# DA16200_Thing_Plus.net
KiCad netlist of a schematic drawn in EAGLE
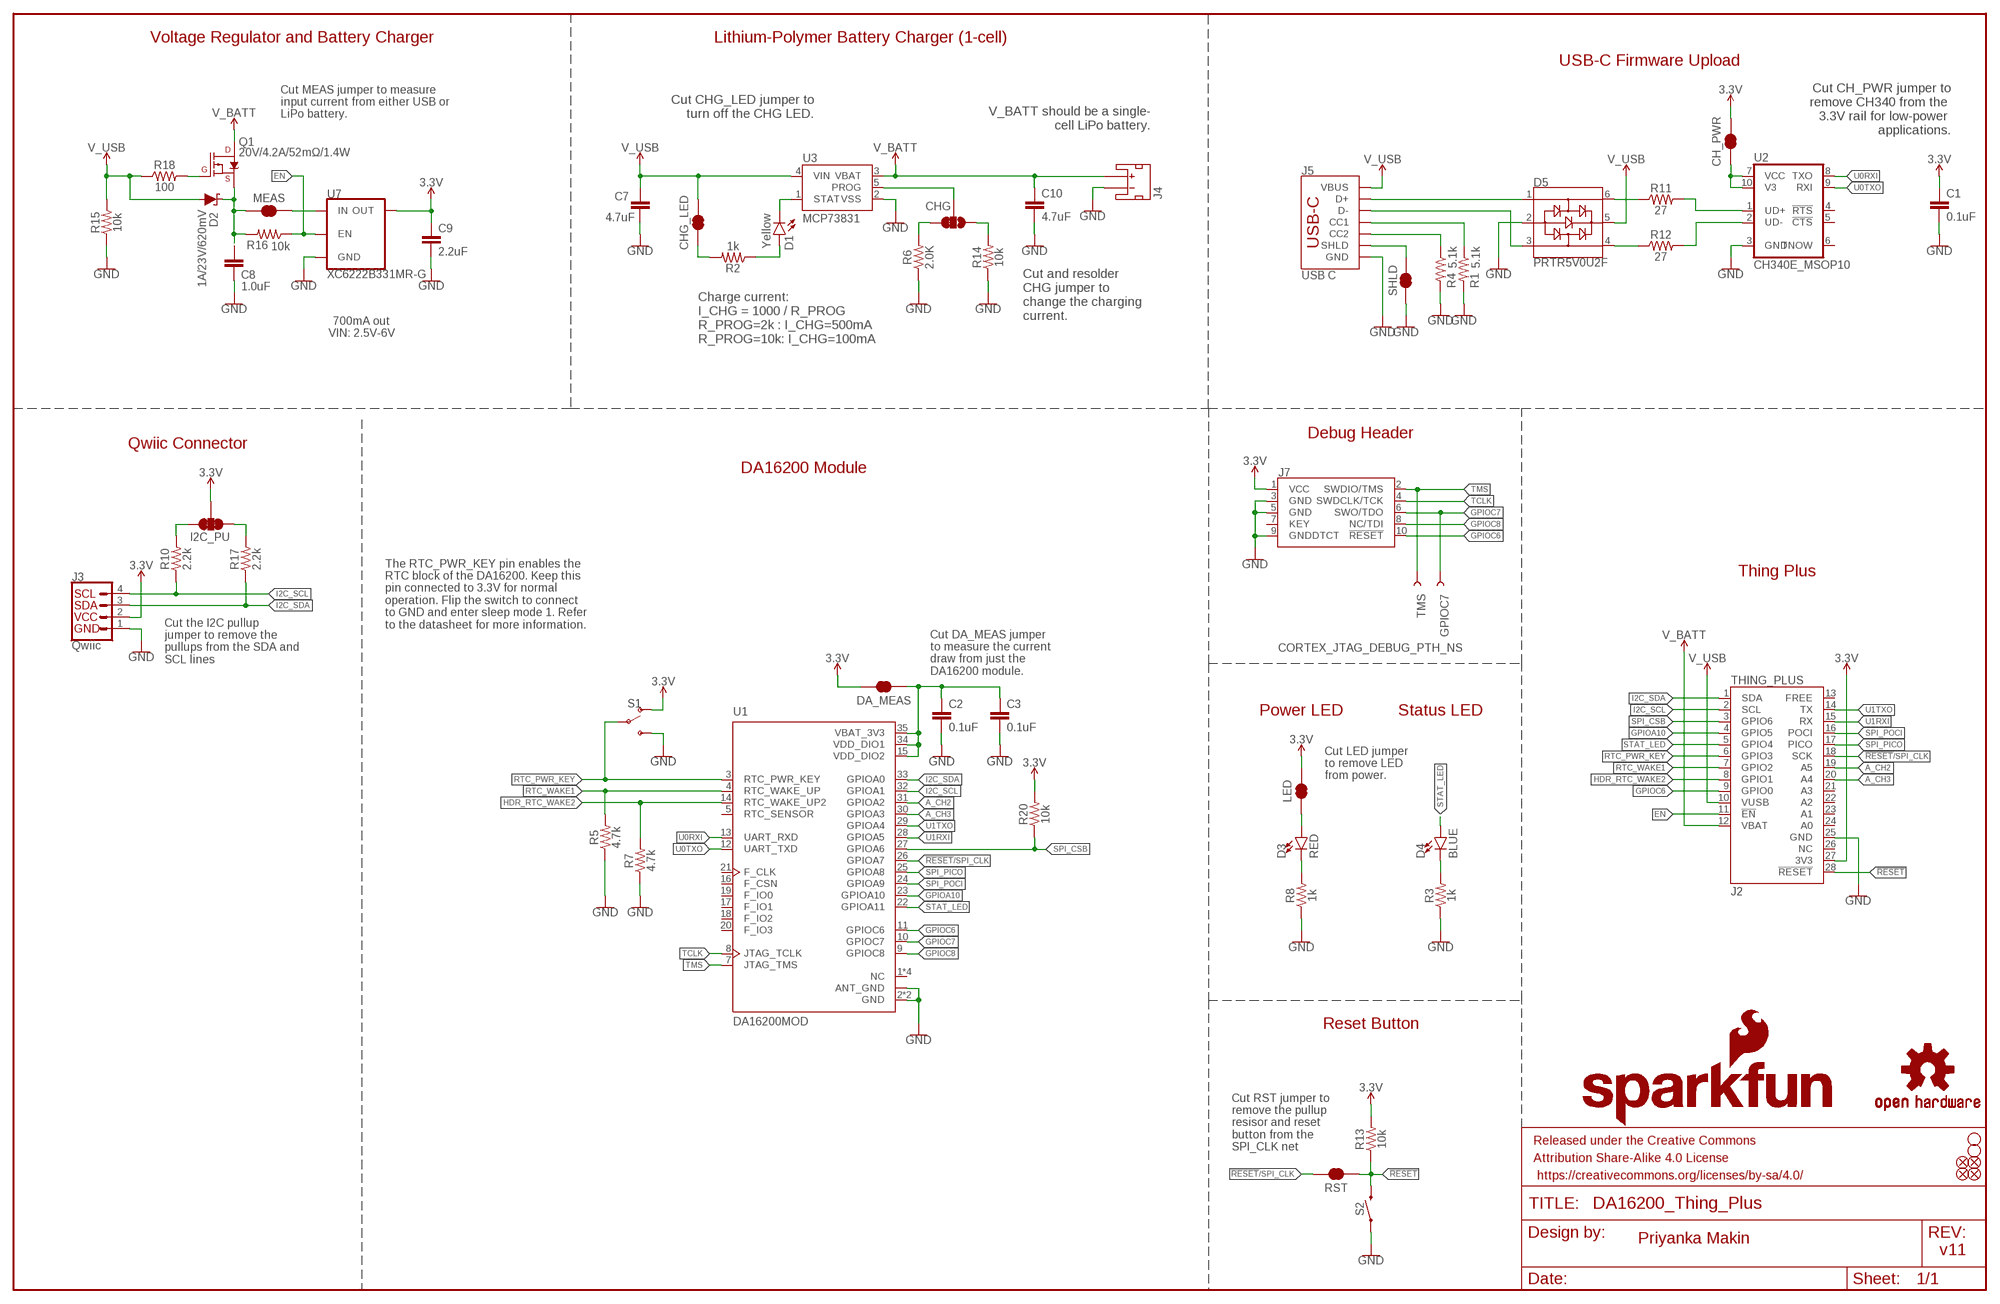
[diagram p0: schematic, sheet 1]

(export (version "E")
  (design (tool "Eeschema 10.0.6"))
  (components
    (comp (ref "C1")
      (value "0.1uF")
      (footprint "eagle-import:0402-TIGHT")
      (libsource (lib "eagle-import") (part "0.1UF-0402T-16V-10%"))
    )
    (comp (ref "C2")
      (value "0.1uF")
      (footprint "eagle-import:0402-TIGHT")
      (libsource (lib "eagle-import") (part "0.1UF-0402T-16V-10%"))
    )
    (comp (ref "C3")
      (value "0.1uF")
      (footprint "eagle-import:0402-TIGHT")
      (libsource (lib "eagle-import") (part "0.1UF-0402T-16V-10%"))
    )
    (comp (ref "C7")
      (value "4.7uF")
      (footprint "eagle-import:0402-TIGHT")
      (libsource (lib "eagle-import") (part "4.7UF-0402_TIGHT-6.3V-20%-X5R"))
    )
    (comp (ref "C8")
      (value "1.0uF")
      (footprint "eagle-import:0402-TIGHT")
      (libsource (lib "eagle-import") (part "1.0UF-0402T-16V-10%"))
    )
    (comp (ref "C9")
      (value "2.2uF")
      (footprint "eagle-import:0402-TIGHT")
      (libsource (lib "eagle-import") (part "2.2UF-0402_TIGHT-10V-10%-X5R"))
    )
    (comp (ref "C10")
      (value "4.7uF")
      (footprint "eagle-import:0402-TIGHT")
      (libsource (lib "eagle-import") (part "4.7UF-0402_TIGHT-6.3V-20%-X5R"))
    )
    (comp (ref "CHG")
      (value "JUMPER-SMT_3_1-NC_TRACE_SILK")
      (footprint "eagle-import:SMT-JUMPER_3_1-NC_TRACE_SILK")
      (libsource (lib "eagle-import") (part "JUMPER-SMT_3_1-NC_TRACE_SILK"))
    )
    (comp (ref "CHG_LED")
      (value "JUMPER-SMT_2_NC_TRACE_SILK")
      (footprint "eagle-import:SMT-JUMPER_2_NC_TRACE_SILK")
      (libsource (lib "eagle-import") (part "JUMPER-SMT_2_NC_TRACE_SILK"))
    )
    (comp (ref "CH_PWR")
      (value "JUMPER-SMT_2_NC_TRACE_SILK")
      (footprint "eagle-import:SMT-JUMPER_2_NC_TRACE_SILK")
      (libsource (lib "eagle-import") (part "JUMPER-SMT_2_NC_TRACE_SILK"))
    )
    (comp (ref "D1")
      (value "Yellow")
      (footprint "eagle-import:LED-0603")
      (libsource (lib "eagle-import") (part "LED-YELLOW0603"))
    )
    (comp (ref "D2")
      (value "1A/23V/620mV")
      (footprint "eagle-import:SOD-323")
      (libsource (lib "eagle-import") (part "DIODE-SCHOTTKY-BAT20J"))
    )
    (comp (ref "D3")
      (value "RED")
      (footprint "eagle-import:LED-0603")
      (libsource (lib "eagle-import") (part "LED-RED0603"))
    )
    (comp (ref "D4")
      (value "BLUE")
      (footprint "eagle-import:LED-0603")
      (libsource (lib "eagle-import") (part "LED-BLUE0603"))
    )
    (comp (ref "D5")
      (value "PRTR5V0U2F")
      (footprint "eagle-import:SOT886")
      (libsource (lib "eagle-import") (part "PRTR5V0U2F"))
    )
    (comp (ref "DA_MEAS")
      (value "JUMPER-SMT_2_NC_TRACE_SILK")
      (footprint "eagle-import:SMT-JUMPER_2_NC_TRACE_SILK")
      (libsource (lib "eagle-import") (part "JUMPER-SMT_2_NC_TRACE_SILK"))
    )
    (comp (ref "FD1")
      (value "FIDUCIALUFIDUCIAL")
      (footprint "eagle-import:FIDUCIAL-MICRO")
      (libsource (lib "eagle-import") (part "FIDUCIALUFIDUCIAL"))
    )
    (comp (ref "FD2")
      (value "FIDUCIALUFIDUCIAL")
      (footprint "eagle-import:FIDUCIAL-MICRO")
      (libsource (lib "eagle-import") (part "FIDUCIALUFIDUCIAL"))
    )
    (comp (ref "FD3")
      (value "FIDUCIALUFIDUCIAL")
      (footprint "eagle-import:FIDUCIAL-MICRO")
      (libsource (lib "eagle-import") (part "FIDUCIALUFIDUCIAL"))
    )
    (comp (ref "FD4")
      (value "FIDUCIALUFIDUCIAL")
      (footprint "eagle-import:FIDUCIAL-MICRO")
      (libsource (lib "eagle-import") (part "FIDUCIALUFIDUCIAL"))
    )
    (comp (ref "FRAME1")
      (value "FRAME-LEDGER")
      (footprint "eagle-import:CREATIVE_COMMONS")
      (libsource (lib "eagle-import") (part "FRAME-LEDGER"))
    )
    (comp (ref "GPIOC7")
      (value "TEST-POINT3")
      (footprint "eagle-import:PAD.03X.03")
      (libsource (lib "eagle-import") (part "TEST-POINT3"))
    )
    (comp (ref "H3")
      (value "STAND-OFF")
      (footprint "eagle-import:STAND-OFF")
      (libsource (lib "eagle-import") (part "STAND-OFF"))
    )
    (comp (ref "H4")
      (value "STAND-OFF")
      (footprint "eagle-import:STAND-OFF")
      (libsource (lib "eagle-import") (part "STAND-OFF"))
    )
    (comp (ref "I2C_PU")
      (value "JUMPER-SMT_3_2-NC_TRACE_SILK")
      (footprint "eagle-import:SMT-JUMPER_3_2-NC_TRACE_SILK")
      (libsource (lib "eagle-import") (part "JUMPER-SMT_3_2-NC_TRACE_SILK"))
    )
    (comp (ref "J2")
      (value "THING_PLUS")
      (footprint "eagle-import:THING_PLUS")
      (libsource (lib "eagle-import") (part "THING_PLUS"))
    )
    (comp (ref "J3")
      (value "Qwiic")
      (footprint "eagle-import:JST04_1MM_RA")
      (libsource (lib "eagle-import") (part "QWIIC_CONNECTORJS-1MM"))
    )
    (comp (ref "J4")
      (value "JST_2MM_MALE")
      (footprint "eagle-import:JST-2-SMD")
      (libsource (lib "eagle-import") (part "JST_2MM_MALE"))
    )
    (comp (ref "J5")
      (value "USB C")
      (footprint "eagle-import:USB-C-16P-4LAYER-ISOLATED")
      (libsource (lib "eagle-import") (part "USB_C_4-LAYER-ISOLATED"))
    )
    (comp (ref "J7")
      (value "CORTEX_JTAG_DEBUG_PTH_NS")
      (footprint "eagle-import:2X5-PTH-1.27MM-NO_SILK")
      (libsource (lib "eagle-import") (part "CORTEX_JTAG_DEBUG_PTH_NS"))
    )
    (comp (ref "LED")
      (value "JUMPER-SMT_2_NC_TRACE_SILK")
      (footprint "eagle-import:SMT-JUMPER_2_NC_TRACE_SILK")
      (libsource (lib "eagle-import") (part "JUMPER-SMT_2_NC_TRACE_SILK"))
    )
    (comp (ref "LOGO1")
      (value "OSHW-LOGOS")
      (footprint "eagle-import:OSHW-LOGO-S")
      (libsource (lib "eagle-import") (part "OSHW-LOGOS"))
    )
    (comp (ref "LOGO2")
      (value "SFE_LOGO_NAME_FLAME.1_INCH")
      (footprint "eagle-import:SFE_LOGO_NAME_FLAME_.1")
      (libsource (lib "eagle-import") (part "SFE_LOGO_NAME_FLAME.1_INCH"))
    )
    (comp (ref "MEAS")
      (value "JUMPER-COMBO_2_NC_TRACE")
      (footprint "eagle-import:COMBO-JUMPER_2_NC_TRACE")
      (libsource (lib "eagle-import") (part "JUMPER-COMBO_2_NC_TRACE"))
    )
    (comp (ref "Q1")
      (value "20V/4.2A/52mΩ/1.4W")
      (footprint "eagle-import:SOT23-3")
      (libsource (lib "eagle-import") (part "MOSFET_PCH-DMG2305UX-7"))
    )
    (comp (ref "R1")
      (value "5.1k")
      (footprint "eagle-import:0402-TIGHT")
      (libsource (lib "eagle-import") (part "5.1KOHM-0402T-1/16W-1%"))
    )
    (comp (ref "R2")
      (value "1k")
      (footprint "eagle-import:0402-TIGHT")
      (libsource (lib "eagle-import") (part "1KOHM-0402T-1/16W-1%"))
    )
    (comp (ref "R3")
      (value "1k")
      (footprint "eagle-import:0402-TIGHT")
      (libsource (lib "eagle-import") (part "1KOHM-0402T-1/16W-1%"))
    )
    (comp (ref "R4")
      (value "5.1k")
      (footprint "eagle-import:0402-TIGHT")
      (libsource (lib "eagle-import") (part "5.1KOHM-0402T-1/16W-1%"))
    )
    (comp (ref "R5")
      (value "4.7k")
      (footprint "eagle-import:0402-TIGHT")
      (libsource (lib "eagle-import") (part "4.7KOHM-0402T-1/16W-1%"))
    )
    (comp (ref "R6")
      (value "2.0K")
      (footprint "eagle-import:0402-TIGHT")
      (libsource (lib "eagle-import") (part "2.0KOHM-0402T-1/16W-1%"))
    )
    (comp (ref "R7")
      (value "4.7k")
      (footprint "eagle-import:0402-TIGHT")
      (libsource (lib "eagle-import") (part "4.7KOHM-0402T-1/16W-1%"))
    )
    (comp (ref "R8")
      (value "1k")
      (footprint "eagle-import:0402-TIGHT")
      (libsource (lib "eagle-import") (part "1KOHM-0402T-1/16W-1%"))
    )
    (comp (ref "R10")
      (value "2.2k")
      (footprint "eagle-import:0402-TIGHT")
      (libsource (lib "eagle-import") (part "2.2KOHM-0402T-1/16W-1%"))
    )
    (comp (ref "R11")
      (value "27")
      (footprint "eagle-import:0402-TIGHT")
      (libsource (lib "eagle-import") (part "27OHM"))
    )
    (comp (ref "R12")
      (value "27")
      (footprint "eagle-import:0402-TIGHT")
      (libsource (lib "eagle-import") (part "27OHM"))
    )
    (comp (ref "R13")
      (value "10k")
      (footprint "eagle-import:0402-TIGHT")
      (libsource (lib "eagle-import") (part "10KOHM-0402T-1/16W-1%"))
    )
    (comp (ref "R14")
      (value "10k")
      (footprint "eagle-import:0402-TIGHT")
      (libsource (lib "eagle-import") (part "10KOHM-0402T-1/16W-1%"))
    )
    (comp (ref "R15")
      (value "10k")
      (footprint "eagle-import:0402-TIGHT")
      (libsource (lib "eagle-import") (part "10KOHM-0402T-1/16W-1%"))
    )
    (comp (ref "R16")
      (value "10k")
      (footprint "eagle-import:0402-TIGHT")
      (libsource (lib "eagle-import") (part "10KOHM-0402T-1/16W-1%"))
    )
    (comp (ref "R17")
      (value "2.2k")
      (footprint "eagle-import:0402-TIGHT")
      (libsource (lib "eagle-import") (part "2.2KOHM-0402T-1/16W-1%"))
    )
    (comp (ref "R18")
      (value "100")
      (footprint "eagle-import:0402-TIGHT")
      (libsource (lib "eagle-import") (part "100OHM-0402-TIGHT-1/16W-1%"))
    )
    (comp (ref "R20")
      (value "10k")
      (footprint "eagle-import:0402-TIGHT")
      (libsource (lib "eagle-import") (part "10KOHM-0402T-1/16W-1%"))
    )
    (comp (ref "RST")
      (value "JUMPER-SMT_2_NC_TRACE_SILK")
      (footprint "eagle-import:SMT-JUMPER_2_NC_TRACE_SILK")
      (libsource (lib "eagle-import") (part "JUMPER-SMT_2_NC_TRACE_SILK"))
    )
    (comp (ref "S1")
      (value "SWITCH-SPDT-SMD-AYZ0202")
      (footprint "eagle-import:SWITCH_DPDT_SMD_AYZ0202")
      (libsource (lib "eagle-import") (part "SWITCH-SPDT-SMD-AYZ0202"))
    )
    (comp (ref "S2")
      (value "MOMENTARY-SWITCH-SPST-SMD-5.2MM-TALL")
      (footprint "eagle-import:TACTILE_SWITCH_SMD_5.2MM")
      (libsource (lib "eagle-import") (part "MOMENTARY-SWITCH-SPST-SMD-5.2MM-TALL"))
    )
    (comp (ref "SHLD")
      (value "JUMPER-SMT_2_NC_TRACE_SILK")
      (footprint "eagle-import:SMT-JUMPER_2_NC_TRACE_SILK")
      (libsource (lib "eagle-import") (part "JUMPER-SMT_2_NC_TRACE_SILK"))
    )
    (comp (ref "TMS")
      (value "TEST-POINT3")
      (footprint "eagle-import:PAD.03X.03")
      (libsource (lib "eagle-import") (part "TEST-POINT3"))
    )
    (comp (ref "U1")
      (value "DA16200MOD")
      (footprint "eagle-import:XCVR_DA16200MOD-AAC4WA32")
      (libsource (lib "eagle-import") (part "DA16200MOD-AAC4WA32"))
    )
    (comp (ref "U2")
      (value "CH340E_MSOP10")
      (footprint "eagle-import:MSOP10")
      (libsource (lib "eagle-import") (part "CH340E_MSOP10"))
    )
    (comp (ref "U3")
      (value "MCP73831")
      (footprint "eagle-import:SOT23-5")
      (libsource (lib "eagle-import") (part "MCP73831"))
    )
    (comp (ref "U7")
      (value "XC6222B331MR-G")
      (footprint "eagle-import:SOT23-5")
      (libsource (lib "eagle-import") (part "XC6222B331MR-G"))
    )
  )
  (nets
    (net (code "1") (name "/~{RESET}") (class "Default")
      (node (ref "J2") (pin "28") (pinfunction "~{RESET}_28") (pintype "bidirectional"))
      (node (ref "R13") (pin "1") (pinfunction "1_1") (pintype "passive"))
      (node (ref "RST") (pin "1") (pinfunction "1_1") (pintype "passive"))
      (node (ref "S2") (pin "3") (pinfunction "2_3") (pintype "passive"))
    )
    (net (code "2") (name "/~{RESET}{slash}SPI_CLK") (class "Default")
      (node (ref "J2") (pin "18") (pinfunction "SCK_18") (pintype "bidirectional"))
      (node (ref "RST") (pin "2") (pinfunction "2_2") (pintype "passive"))
      (node (ref "U1") (pin "26") (pinfunction "GPIOA7_26") (pintype "bidirectional"))
    )
    (net (code "3") (name "3.3V") (class "Default")
      (node (ref "C1") (pin "1") (pinfunction "1_1") (pintype "passive"))
      (node (ref "C9") (pin "1") (pinfunction "1_1") (pintype "passive"))
      (node (ref "CH_PWR") (pin "2") (pinfunction "2_2") (pintype "passive"))
      (node (ref "DA_MEAS") (pin "2") (pinfunction "2_2") (pintype "passive"))
      (node (ref "I2C_PU") (pin "2") (pinfunction "2_2") (pintype "passive"))
      (node (ref "J2") (pin "27") (pinfunction "3V3_27") (pintype "bidirectional"))
      (node (ref "J3") (pin "2") (pinfunction "2_2") (pintype "power_in"))
      (node (ref "J7") (pin "1") (pinfunction "VCC_1") (pintype "bidirectional"))
      (node (ref "LED") (pin "2") (pinfunction "2_2") (pintype "passive"))
      (node (ref "R13") (pin "2") (pinfunction "2_2") (pintype "passive"))
      (node (ref "R20") (pin "2") (pinfunction "2_2") (pintype "passive"))
      (node (ref "S1") (pin "1") (pinfunction "O_1") (pintype "passive"))
      (node (ref "U7") (pin "5") (pinfunction "OUT_5") (pintype "passive"))
    )
    (net (code "4") (name "A_CH2") (class "Default")
      (node (ref "J2") (pin "19") (pinfunction "A5_19") (pintype "bidirectional"))
      (node (ref "U1") (pin "31") (pinfunction "GPIOA2_31") (pintype "bidirectional"))
    )
    (net (code "5") (name "A_CH3") (class "Default")
      (node (ref "J2") (pin "20") (pinfunction "A4_20") (pintype "bidirectional"))
      (node (ref "U1") (pin "30") (pinfunction "GPIOA3_30") (pintype "bidirectional"))
    )
    (net (code "6") (name "EN") (class "Default")
      (node (ref "J2") (pin "11") (pinfunction "~{EN}_11") (pintype "bidirectional"))
      (node (ref "R16") (pin "1") (pinfunction "1_1") (pintype "passive"))
      (node (ref "U7") (pin "3") (pinfunction "EN_3") (pintype "input"))
    )
    (net (code "7") (name "GND") (class "Default")
      (node (ref "C1") (pin "2") (pinfunction "2_2") (pintype "passive"))
      (node (ref "C10") (pin "2") (pinfunction "2_2") (pintype "passive"))
      (node (ref "C2") (pin "2") (pinfunction "2_2") (pintype "passive"))
      (node (ref "C3") (pin "2") (pinfunction "2_2") (pintype "passive"))
      (node (ref "C7") (pin "2") (pinfunction "2_2") (pintype "passive"))
      (node (ref "C8") (pin "2") (pinfunction "2_2") (pintype "passive"))
      (node (ref "C9") (pin "2") (pinfunction "2_2") (pintype "passive"))
      (node (ref "D5") (pin "2") (pinfunction "2_2") (pintype "power_in"))
      (node (ref "J2") (pin "25") (pinfunction "GND_25") (pintype "bidirectional"))
      (node (ref "J3") (pin "1") (pinfunction "1_1") (pintype "power_in"))
      (node (ref "J4") (pin "1") (pinfunction "-_1") (pintype "bidirectional"))
      (node (ref "J5") (pin "GND") (pinfunction "GND_GND") (pintype "bidirectional"))
      (node (ref "J5") (pin "GND2") (pinfunction "GND_GND2") (pintype "bidirectional"))
      (node (ref "J7") (pin "3") (pinfunction "GND_3") (pintype "bidirectional"))
      (node (ref "J7") (pin "5") (pinfunction "GND_5") (pintype "bidirectional"))
      (node (ref "J7") (pin "9") (pinfunction "GNDDTCT_9") (pintype "bidirectional"))
      (node (ref "R1") (pin "2") (pinfunction "2_2") (pintype "passive"))
      (node (ref "R14") (pin "1") (pinfunction "1_1") (pintype "passive"))
      (node (ref "R15") (pin "1") (pinfunction "1_1") (pintype "passive"))
      (node (ref "R3") (pin "1") (pinfunction "1_1") (pintype "passive"))
      (node (ref "R4") (pin "2") (pinfunction "2_2") (pintype "passive"))
      (node (ref "R5") (pin "1") (pinfunction "1_1") (pintype "passive"))
      (node (ref "R6") (pin "1") (pinfunction "1_1") (pintype "passive"))
      (node (ref "R7") (pin "1") (pinfunction "1_1") (pintype "passive"))
      (node (ref "R8") (pin "1") (pinfunction "1_1") (pintype "passive"))
      (node (ref "S1") (pin "3") (pinfunction "S_3") (pintype "passive"))
      (node (ref "S2") (pin "1") (pinfunction "1_1") (pintype "passive"))
      (node (ref "SHLD") (pin "1") (pinfunction "1_1") (pintype "passive"))
      (node (ref "U1") (pin "2") (pinfunction "GND_2") (pintype "power_in"))
      (node (ref "U1") (pin "ANT_GND") (pinfunction "ANT_GND_ANT_GND") (pintype "power_in"))
      (node (ref "U1") (pin "GND") (pinfunction "GND_GND") (pintype "power_in"))
      (node (ref "U2") (pin "3") (pinfunction "GND_3") (pintype "bidirectional"))
      (node (ref "U3") (pin "2") (pinfunction "VSS_2") (pintype "power_in"))
      (node (ref "U7") (pin "2") (pinfunction "GND_2") (pintype "input"))
    )
    (net (code "8") (name "GPIOA10") (class "Default")
      (node (ref "J2") (pin "4") (pinfunction "GPIO5_4") (pintype "bidirectional"))
      (node (ref "U1") (pin "23") (pinfunction "GPIOA10_23") (pintype "bidirectional"))
    )
    (net (code "9") (name "GPIOC6") (class "Default")
      (node (ref "J2") (pin "9") (pinfunction "GPIO0_9") (pintype "bidirectional"))
      (node (ref "J7") (pin "10") (pinfunction "~{RESET}_10") (pintype "bidirectional"))
      (node (ref "U1") (pin "11") (pinfunction "GPIOC6_11") (pintype "bidirectional"))
    )
    (net (code "10") (name "GPIOC7") (class "Default")
      (node (ref "GPIOC7") (pin "1") (pinfunction "1_1") (pintype "bidirectional"))
      (node (ref "J7") (pin "6") (pinfunction "SWO/TDO_6") (pintype "bidirectional"))
      (node (ref "U1") (pin "10") (pinfunction "GPIOC7_10") (pintype "bidirectional"))
    )
    (net (code "11") (name "GPIOC8") (class "Default")
      (node (ref "J7") (pin "8") (pinfunction "NC/TDI_8") (pintype "bidirectional"))
      (node (ref "U1") (pin "9") (pinfunction "GPIOC8_9") (pintype "bidirectional"))
    )
    (net (code "12") (name "HDR_RTC_WAKE2") (class "Default")
      (node (ref "J2") (pin "8") (pinfunction "GPIO1_8") (pintype "bidirectional"))
      (node (ref "R7") (pin "2") (pinfunction "2_2") (pintype "passive"))
      (node (ref "U1") (pin "14") (pinfunction "RTC_WAKE_UP2_14") (pintype "input"))
    )
    (net (code "13") (name "I2C_SCL") (class "Default")
      (node (ref "J2") (pin "2") (pinfunction "SCL_2") (pintype "bidirectional"))
      (node (ref "J3") (pin "4") (pinfunction "4_4") (pintype "passive"))
      (node (ref "R10") (pin "1") (pinfunction "1_1") (pintype "passive"))
      (node (ref "U1") (pin "32") (pinfunction "GPIOA1_32") (pintype "bidirectional"))
    )
    (net (code "14") (name "I2C_SDA") (class "Default")
      (node (ref "J2") (pin "1") (pinfunction "SDA_1") (pintype "bidirectional"))
      (node (ref "J3") (pin "3") (pinfunction "3_3") (pintype "passive"))
      (node (ref "R17") (pin "1") (pinfunction "1_1") (pintype "passive"))
      (node (ref "U1") (pin "33") (pinfunction "GPIOA0_33") (pintype "bidirectional"))
    )
    (net (code "15") (name "Net-(CHG-Pad1)") (class "Default")
      (node (ref "CHG") (pin "1") (pinfunction "1_1") (pintype "passive"))
      (node (ref "R14") (pin "2") (pinfunction "2_2") (pintype "passive"))
    )
    (net (code "16") (name "Net-(CHG-Pad3)") (class "Default")
      (node (ref "CHG") (pin "3") (pinfunction "3_3") (pintype "passive"))
      (node (ref "R6") (pin "2") (pinfunction "2_2") (pintype "passive"))
    )
    (net (code "17") (name "Net-(CHG_LED-Pad1)") (class "Default")
      (node (ref "CHG_LED") (pin "1") (pinfunction "1_1") (pintype "passive"))
      (node (ref "R2") (pin "2") (pinfunction "2_2") (pintype "passive"))
    )
    (net (code "18") (name "Net-(D1-PadA)") (class "Default")
      (node (ref "D1") (pin "A") (pinfunction "A_A") (pintype "passive"))
      (node (ref "R2") (pin "1") (pinfunction "1_1") (pintype "passive"))
    )
    (net (code "19") (name "Net-(D3-PadA)") (class "Default")
      (node (ref "D3") (pin "A") (pinfunction "A_A") (pintype "passive"))
      (node (ref "LED") (pin "1") (pinfunction "1_1") (pintype "passive"))
    )
    (net (code "20") (name "Net-(D3-PadC)") (class "Default")
      (node (ref "D3") (pin "C") (pinfunction "C_C") (pintype "passive"))
      (node (ref "R8") (pin "2") (pinfunction "2_2") (pintype "passive"))
    )
    (net (code "21") (name "Net-(D4-PadC)") (class "Default")
      (node (ref "D4") (pin "C") (pinfunction "C_C") (pintype "passive"))
      (node (ref "R3") (pin "2") (pinfunction "2_2") (pintype "passive"))
    )
    (net (code "22") (name "Net-(D5-Pad1)") (class "Default")
      (node (ref "D5") (pin "1") (pinfunction "1_1") (pintype "bidirectional"))
      (node (ref "J5") (pin "A6") (pinfunction "D+_A6") (pintype "bidirectional"))
      (node (ref "J5") (pin "B6") (pinfunction "D+_B6") (pintype "bidirectional"))
    )
    (net (code "23") (name "Net-(D5-Pad3)") (class "Default")
      (node (ref "D5") (pin "3") (pinfunction "3_3") (pintype "bidirectional"))
      (node (ref "J5") (pin "A7") (pinfunction "D-_A7") (pintype "bidirectional"))
      (node (ref "J5") (pin "B7") (pinfunction "D-_B7") (pintype "bidirectional"))
    )
    (net (code "24") (name "Net-(D5-Pad4)") (class "Default")
      (node (ref "D5") (pin "4") (pinfunction "4_4") (pintype "bidirectional"))
      (node (ref "R12") (pin "1") (pinfunction "1_1") (pintype "passive"))
    )
    (net (code "25") (name "Net-(D5-Pad6)") (class "Default")
      (node (ref "D5") (pin "6") (pinfunction "6_6") (pintype "bidirectional"))
      (node (ref "R11") (pin "1") (pinfunction "1_1") (pintype "passive"))
    )
    (net (code "26") (name "Net-(I2C_PU-Pad1)") (class "Default")
      (node (ref "I2C_PU") (pin "1") (pinfunction "1_1") (pintype "passive"))
      (node (ref "R17") (pin "2") (pinfunction "2_2") (pintype "passive"))
    )
    (net (code "27") (name "Net-(I2C_PU-Pad3)") (class "Default")
      (node (ref "I2C_PU") (pin "3") (pinfunction "3_3") (pintype "passive"))
      (node (ref "R10") (pin "2") (pinfunction "2_2") (pintype "passive"))
    )
    (net (code "28") (name "Net-(J5-CC1)") (class "Default")
      (node (ref "J5") (pin "A5") (pinfunction "CC1_A5") (pintype "bidirectional"))
      (node (ref "R1") (pin "1") (pinfunction "1_1") (pintype "passive"))
    )
    (net (code "29") (name "Net-(J5-CC2)") (class "Default")
      (node (ref "J5") (pin "B5") (pinfunction "CC2_B5") (pintype "bidirectional"))
      (node (ref "R4") (pin "1") (pinfunction "1_1") (pintype "passive"))
    )
    (net (code "30") (name "Net-(J5-SHLD-PadSHLD1)") (class "Default")
      (node (ref "J5") (pin "SHLD1") (pinfunction "SHLD_SHLD1") (pintype "bidirectional"))
      (node (ref "J5") (pin "SHLD2") (pinfunction "SHLD_SHLD2") (pintype "bidirectional"))
      (node (ref "J5") (pin "SHLD3") (pinfunction "SHLD_SHLD3") (pintype "bidirectional"))
      (node (ref "J5") (pin "SHLD4") (pinfunction "SHLD_SHLD4") (pintype "bidirectional"))
      (node (ref "J5") (pin "SHLD5") (pinfunction "SHLD_SHLD5") (pintype "bidirectional"))
      (node (ref "J5") (pin "SHLD6") (pinfunction "SHLD_SHLD6") (pintype "bidirectional"))
      (node (ref "J5") (pin "SHLD7") (pinfunction "SHLD_SHLD7") (pintype "bidirectional"))
      (node (ref "J5") (pin "SHLD8") (pinfunction "SHLD_SHLD8") (pintype "bidirectional"))
      (node (ref "SHLD") (pin "2") (pinfunction "2_2") (pintype "passive"))
    )
    (net (code "31") (name "Net-(Q1-G)") (class "Default")
      (node (ref "Q1") (pin "1") (pinfunction "G_1") (pintype "bidirectional"))
      (node (ref "R18") (pin "2") (pinfunction "2_2") (pintype "passive"))
    )
    (net (code "32") (name "Net-(Q1-S)") (class "Default")
      (node (ref "C8") (pin "1") (pinfunction "1_1") (pintype "passive"))
      (node (ref "D2") (pin "C") (pinfunction "C_C") (pintype "passive"))
      (node (ref "MEAS") (pin "1") (pinfunction "1_1") (pintype "passive"))
      (node (ref "MEAS") (pin "3") (pinfunction "1_3") (pintype "passive"))
      (node (ref "Q1") (pin "2") (pinfunction "S_2") (pintype "bidirectional"))
      (node (ref "R16") (pin "2") (pinfunction "2_2") (pintype "passive"))
    )
    (net (code "33") (name "Net-(U1-VBAT_3V3)") (class "Default")
      (node (ref "C2") (pin "1") (pinfunction "1_1") (pintype "passive"))
      (node (ref "C3") (pin "1") (pinfunction "1_1") (pintype "passive"))
      (node (ref "DA_MEAS") (pin "1") (pinfunction "1_1") (pintype "passive"))
      (node (ref "U1") (pin "15") (pinfunction "VDD_DIO2_15") (pintype "power_in"))
      (node (ref "U1") (pin "34") (pinfunction "VDD_DIO1_34") (pintype "power_in"))
      (node (ref "U1") (pin "35") (pinfunction "VBAT_3V3_35") (pintype "power_in"))
    )
    (net (code "34") (name "Net-(U2-UD+)") (class "Default")
      (node (ref "R11") (pin "2") (pinfunction "2_2") (pintype "passive"))
      (node (ref "U2") (pin "1") (pinfunction "UD+_1") (pintype "bidirectional"))
    )
    (net (code "35") (name "Net-(U2-UD-)") (class "Default")
      (node (ref "R12") (pin "2") (pinfunction "2_2") (pintype "passive"))
      (node (ref "U2") (pin "2") (pinfunction "UD-_2") (pintype "bidirectional"))
    )
    (net (code "36") (name "Net-(U2-V3)") (class "Default")
      (node (ref "CH_PWR") (pin "1") (pinfunction "1_1") (pintype "passive"))
      (node (ref "U2") (pin "10") (pinfunction "V3_10") (pintype "bidirectional"))
      (node (ref "U2") (pin "7") (pinfunction "VCC_7") (pintype "bidirectional"))
    )
    (net (code "37") (name "Net-(U3-PROG)") (class "Default")
      (node (ref "CHG") (pin "2") (pinfunction "2_2") (pintype "passive"))
      (node (ref "U3") (pin "5") (pinfunction "PROG_5") (pintype "input"))
    )
    (net (code "38") (name "Net-(U3-STAT)") (class "Default")
      (node (ref "D1") (pin "C") (pinfunction "C_C") (pintype "passive"))
      (node (ref "U3") (pin "1") (pinfunction "STAT_1") (pintype "output"))
    )
    (net (code "39") (name "Net-(U7-IN)") (class "Default")
      (node (ref "MEAS") (pin "2") (pinfunction "2_2") (pintype "passive"))
      (node (ref "MEAS") (pin "4") (pinfunction "2_4") (pintype "passive"))
      (node (ref "U7") (pin "1") (pinfunction "IN_1") (pintype "input"))
    )
    (net (code "40") (name "RTC_PWR_KEY") (class "Default")
      (node (ref "J2") (pin "6") (pinfunction "GPIO3_6") (pintype "bidirectional"))
      (node (ref "S1") (pin "2") (pinfunction "P_2") (pintype "passive"))
      (node (ref "U1") (pin "3") (pinfunction "RTC_PWR_KEY_3") (pintype "input"))
    )
    (net (code "41") (name "RTC_WAKE1") (class "Default")
      (node (ref "J2") (pin "7") (pinfunction "GPIO2_7") (pintype "bidirectional"))
      (node (ref "R5") (pin "2") (pinfunction "2_2") (pintype "passive"))
      (node (ref "U1") (pin "4") (pinfunction "RTC_WAKE_UP_4") (pintype "input"))
    )
    (net (code "42") (name "SPI_CSB") (class "Default")
      (node (ref "J2") (pin "3") (pinfunction "GPIO6_3") (pintype "bidirectional"))
      (node (ref "R20") (pin "1") (pinfunction "1_1") (pintype "passive"))
      (node (ref "U1") (pin "27") (pinfunction "GPIOA6_27") (pintype "bidirectional"))
    )
    (net (code "43") (name "SPI_PICO") (class "Default")
      (node (ref "J2") (pin "17") (pinfunction "PICO_17") (pintype "bidirectional"))
      (node (ref "U1") (pin "25") (pinfunction "GPIOA8_25") (pintype "bidirectional"))
    )
    (net (code "44") (name "SPI_POCI") (class "Default")
      (node (ref "J2") (pin "16") (pinfunction "POCI_16") (pintype "bidirectional"))
      (node (ref "U1") (pin "24") (pinfunction "GPIOA9_24") (pintype "bidirectional"))
    )
    (net (code "45") (name "STAT_LED") (class "Default")
      (node (ref "D4") (pin "A") (pinfunction "A_A") (pintype "passive"))
      (node (ref "J2") (pin "5") (pinfunction "GPIO4_5") (pintype "bidirectional"))
      (node (ref "U1") (pin "22") (pinfunction "GPIOA11_22") (pintype "bidirectional"))
    )
    (net (code "46") (name "TCLK") (class "Default")
      (node (ref "J7") (pin "4") (pinfunction "SWDCLK/TCK_4") (pintype "bidirectional"))
      (node (ref "U1") (pin "8") (pinfunction "JTAG_TCLK_8") (pintype "bidirectional"))
    )
    (net (code "47") (name "TMS") (class "Default")
      (node (ref "J7") (pin "2") (pinfunction "SWDIO/TMS_2") (pintype "bidirectional"))
      (node (ref "TMS") (pin "1") (pinfunction "1_1") (pintype "bidirectional"))
      (node (ref "U1") (pin "7") (pinfunction "JTAG_TMS_7") (pintype "bidirectional"))
    )
    (net (code "48") (name "U0RXI") (class "Default")
      (node (ref "U1") (pin "13") (pinfunction "UART_RXD_13") (pintype "input"))
      (node (ref "U2") (pin "8") (pinfunction "TXO_8") (pintype "bidirectional"))
    )
    (net (code "49") (name "U0TXO") (class "Default")
      (node (ref "U1") (pin "12") (pinfunction "UART_TXD_12") (pintype "output"))
      (node (ref "U2") (pin "9") (pinfunction "RXI_9") (pintype "bidirectional"))
    )
    (net (code "50") (name "U1RXI") (class "Default")
      (node (ref "J2") (pin "15") (pinfunction "RX_15") (pintype "bidirectional"))
      (node (ref "U1") (pin "28") (pinfunction "GPIOA5_28") (pintype "bidirectional"))
    )
    (net (code "51") (name "U1TXO") (class "Default")
      (node (ref "J2") (pin "14") (pinfunction "TX_14") (pintype "bidirectional"))
      (node (ref "U1") (pin "29") (pinfunction "GPIOA4_29") (pintype "bidirectional"))
    )
    (net (code "52") (name "V_BATT") (class "Default")
      (node (ref "C10") (pin "1") (pinfunction "1_1") (pintype "passive"))
      (node (ref "J2") (pin "12") (pinfunction "VBAT_12") (pintype "bidirectional"))
      (node (ref "J4") (pin "2") (pinfunction "+_2") (pintype "bidirectional"))
      (node (ref "Q1") (pin "3") (pinfunction "D_3") (pintype "bidirectional"))
      (node (ref "U3") (pin "3") (pinfunction "VBAT_3") (pintype "power_in"))
    )
    (net (code "53") (name "V_USB") (class "Default")
      (node (ref "C7") (pin "1") (pinfunction "1_1") (pintype "passive"))
      (node (ref "CHG_LED") (pin "2") (pinfunction "2_2") (pintype "passive"))
      (node (ref "D2") (pin "A") (pinfunction "A_A") (pintype "passive"))
      (node (ref "D5") (pin "5") (pinfunction "5_5") (pintype "power_in"))
      (node (ref "J2") (pin "10") (pinfunction "VUSB_10") (pintype "bidirectional"))
      (node (ref "J5") (pin "VBUS1") (pinfunction "VBUS_VBUS1") (pintype "bidirectional"))
      (node (ref "J5") (pin "VBUS2") (pinfunction "VBUS_VBUS2") (pintype "bidirectional"))
      (node (ref "R15") (pin "2") (pinfunction "2_2") (pintype "passive"))
      (node (ref "R18") (pin "1") (pinfunction "1_1") (pintype "passive"))
      (node (ref "U3") (pin "4") (pinfunction "VIN_4") (pintype "power_in"))
    )
    (net (code "54") (name "unconnected-(J2-A0-Pad24)") (class "Default")
      (node (ref "J2") (pin "24") (pinfunction "A0_24") (pintype "bidirectional"))
    )
    (net (code "55") (name "unconnected-(J2-A1-Pad23)") (class "Default")
      (node (ref "J2") (pin "23") (pinfunction "A1_23") (pintype "bidirectional"))
    )
    (net (code "56") (name "unconnected-(J2-A2-Pad22)") (class "Default")
      (node (ref "J2") (pin "22") (pinfunction "A2_22") (pintype "bidirectional"))
    )
    (net (code "57") (name "unconnected-(J2-A3-Pad21)") (class "Default")
      (node (ref "J2") (pin "21") (pinfunction "A3_21") (pintype "bidirectional"))
    )
    (net (code "58") (name "unconnected-(J2-FREE-Pad13)") (class "Default")
      (node (ref "J2") (pin "13") (pinfunction "FREE_13") (pintype "bidirectional"))
    )
    (net (code "59") (name "unconnected-(J2-NC-Pad26)") (class "Default")
      (node (ref "J2") (pin "26") (pinfunction "NC_26") (pintype "bidirectional"))
    )
    (net (code "60") (name "unconnected-(J4-PAD1-PadNC1)") (class "Default")
      (node (ref "J4") (pin "NC1") (pinfunction "PAD1_NC1") (pintype "bidirectional"))
    )
    (net (code "61") (name "unconnected-(J4-PAD2-PadNC2)") (class "Default")
      (node (ref "J4") (pin "NC2") (pinfunction "PAD2_NC2") (pintype "bidirectional"))
    )
    (net (code "62") (name "unconnected-(J7-KEY-Pad7)") (class "Default")
      (node (ref "J7") (pin "7") (pinfunction "KEY_7") (pintype "bidirectional"))
    )
    (net (code "63") (name "unconnected-(U1-F_CLK-Pad21)") (class "Default")
      (node (ref "U1") (pin "21") (pinfunction "F_CLK_21") (pintype "bidirectional"))
    )
    (net (code "64") (name "unconnected-(U1-F_CSN-Pad16)") (class "Default")
      (node (ref "U1") (pin "16") (pinfunction "F_CSN_16") (pintype "bidirectional"))
    )
    (net (code "65") (name "unconnected-(U1-F_IO0-Pad19)") (class "Default")
      (node (ref "U1") (pin "19") (pinfunction "F_IO0_19") (pintype "bidirectional"))
    )
    (net (code "66") (name "unconnected-(U1-F_IO1-Pad17)") (class "Default")
      (node (ref "U1") (pin "17") (pinfunction "F_IO1_17") (pintype "bidirectional"))
    )
    (net (code "67") (name "unconnected-(U1-F_IO2-Pad18)") (class "Default")
      (node (ref "U1") (pin "18") (pinfunction "F_IO2_18") (pintype "bidirectional"))
    )
    (net (code "68") (name "unconnected-(U1-F_IO3-Pad20)") (class "Default")
      (node (ref "U1") (pin "20") (pinfunction "F_IO3_20") (pintype "bidirectional"))
    )
    (net (code "69") (name "unconnected-(U1-NC-Pad1)") (class "Default")
      (node (ref "U1") (pin "1") (pinfunction "NC_1") (pintype "no_connect"))
    )
    (net (code "70") (name "unconnected-(U1-NC-Pad6)") (class "Default")
      (node (ref "U1") (pin "6") (pinfunction "NC_6") (pintype "no_connect"))
    )
    (net (code "71") (name "unconnected-(U1-NC-Pad36)") (class "Default")
      (node (ref "U1") (pin "36") (pinfunction "NC_36") (pintype "no_connect"))
    )
    (net (code "72") (name "unconnected-(U1-NC-Pad37)") (class "Default")
      (node (ref "U1") (pin "37") (pinfunction "NC_37") (pintype "no_connect"))
    )
    (net (code "73") (name "unconnected-(U1-RTC_SENSOR-Pad5)") (class "Default")
      (node (ref "U1") (pin "5") (pinfunction "RTC_SENSOR_5") (pintype "output"))
    )
    (net (code "74") (name "unconnected-(U2-TNOW-Pad6)") (class "Default")
      (node (ref "U2") (pin "6") (pinfunction "TNOW_6") (pintype "bidirectional"))
    )
    (net (code "75") (name "unconnected-(U2-~{CTS}-Pad5)") (class "Default")
      (node (ref "U2") (pin "5") (pinfunction "~{CTS}_5") (pintype "bidirectional"))
    )
    (net (code "76") (name "unconnected-(U2-~{RTS}-Pad4)") (class "Default")
      (node (ref "U2") (pin "4") (pinfunction "~{RTS}_4") (pintype "bidirectional"))
    )
  )
)
